# GPIO_adaptator.net
KiCad netlist of a schematic drawn in EAGLE
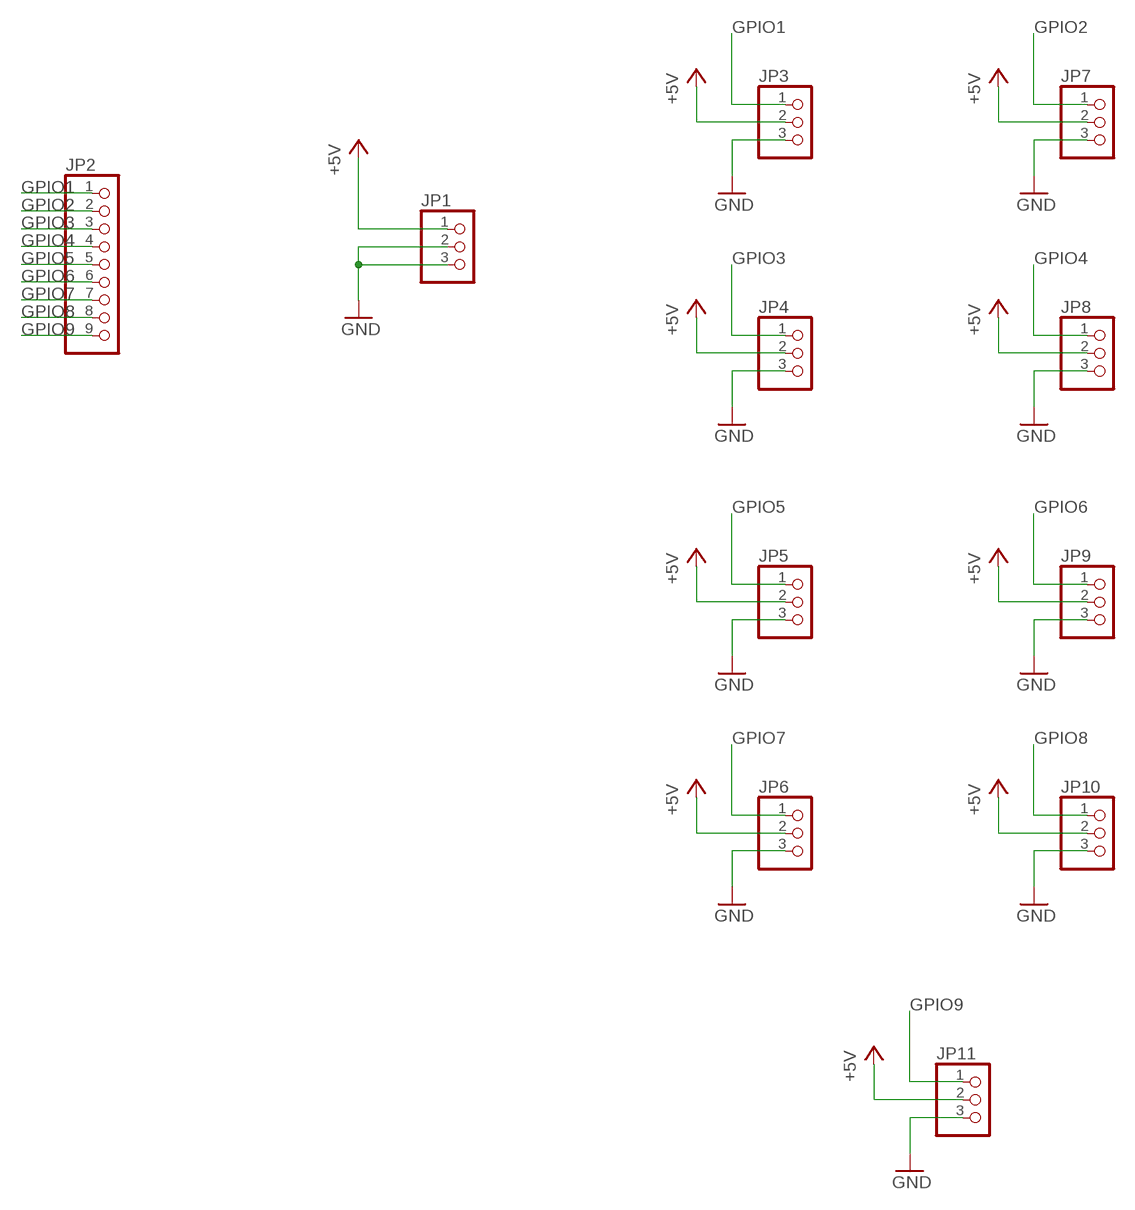
[diagram p0: schematic, sheet 1]

(export (version "E")
  (design (tool "Eeschema 10.0.6"))
  (components
    (comp (ref "JP1")
      (value "PINHD-1X3")
      (footprint "eagle-import:1X03")
      (libsource (lib "eagle-import") (part "PINHD-1X3"))
    )
    (comp (ref "JP2")
      (value "PINHD-1X9")
      (footprint "eagle-import:1X09")
      (libsource (lib "eagle-import") (part "PINHD-1X9"))
    )
    (comp (ref "JP3")
      (value "PINHD-1X3")
      (footprint "eagle-import:1X03")
      (libsource (lib "eagle-import") (part "PINHD-1X3"))
    )
    (comp (ref "JP4")
      (value "PINHD-1X3")
      (footprint "eagle-import:1X03")
      (libsource (lib "eagle-import") (part "PINHD-1X3"))
    )
    (comp (ref "JP5")
      (value "PINHD-1X3")
      (footprint "eagle-import:1X03")
      (libsource (lib "eagle-import") (part "PINHD-1X3"))
    )
    (comp (ref "JP6")
      (value "PINHD-1X3")
      (footprint "eagle-import:1X03")
      (libsource (lib "eagle-import") (part "PINHD-1X3"))
    )
    (comp (ref "JP7")
      (value "PINHD-1X3")
      (footprint "eagle-import:1X03")
      (libsource (lib "eagle-import") (part "PINHD-1X3"))
    )
    (comp (ref "JP8")
      (value "PINHD-1X3")
      (footprint "eagle-import:1X03")
      (libsource (lib "eagle-import") (part "PINHD-1X3"))
    )
    (comp (ref "JP9")
      (value "PINHD-1X3")
      (footprint "eagle-import:1X03")
      (libsource (lib "eagle-import") (part "PINHD-1X3"))
    )
    (comp (ref "JP10")
      (value "PINHD-1X3")
      (footprint "eagle-import:1X03")
      (libsource (lib "eagle-import") (part "PINHD-1X3"))
    )
    (comp (ref "JP11")
      (value "PINHD-1X3")
      (footprint "eagle-import:1X03")
      (libsource (lib "eagle-import") (part "PINHD-1X3"))
    )
  )
  (nets
    (net (code "1") (name "+5V") (class "Default")
      (node (ref "JP1") (pin "1") (pinfunction "1_1") (pintype "passive"))
      (node (ref "JP10") (pin "2") (pinfunction "2_2") (pintype "passive"))
      (node (ref "JP11") (pin "2") (pinfunction "2_2") (pintype "passive"))
      (node (ref "JP3") (pin "2") (pinfunction "2_2") (pintype "passive"))
      (node (ref "JP4") (pin "2") (pinfunction "2_2") (pintype "passive"))
      (node (ref "JP5") (pin "2") (pinfunction "2_2") (pintype "passive"))
      (node (ref "JP6") (pin "2") (pinfunction "2_2") (pintype "passive"))
      (node (ref "JP7") (pin "2") (pinfunction "2_2") (pintype "passive"))
      (node (ref "JP8") (pin "2") (pinfunction "2_2") (pintype "passive"))
      (node (ref "JP9") (pin "2") (pinfunction "2_2") (pintype "passive"))
    )
    (net (code "2") (name "/GPIO1") (class "Default")
      (node (ref "JP2") (pin "1") (pinfunction "1_1") (pintype "passive"))
      (node (ref "JP3") (pin "1") (pinfunction "1_1") (pintype "passive"))
    )
    (net (code "3") (name "/GPIO2") (class "Default")
      (node (ref "JP2") (pin "2") (pinfunction "2_2") (pintype "passive"))
      (node (ref "JP7") (pin "1") (pinfunction "1_1") (pintype "passive"))
    )
    (net (code "4") (name "/GPIO3") (class "Default")
      (node (ref "JP2") (pin "3") (pinfunction "3_3") (pintype "passive"))
      (node (ref "JP4") (pin "1") (pinfunction "1_1") (pintype "passive"))
    )
    (net (code "5") (name "/GPIO4") (class "Default")
      (node (ref "JP2") (pin "4") (pinfunction "4_4") (pintype "passive"))
      (node (ref "JP8") (pin "1") (pinfunction "1_1") (pintype "passive"))
    )
    (net (code "6") (name "/GPIO5") (class "Default")
      (node (ref "JP2") (pin "5") (pinfunction "5_5") (pintype "passive"))
      (node (ref "JP5") (pin "1") (pinfunction "1_1") (pintype "passive"))
    )
    (net (code "7") (name "/GPIO6") (class "Default")
      (node (ref "JP2") (pin "6") (pinfunction "6_6") (pintype "passive"))
      (node (ref "JP9") (pin "1") (pinfunction "1_1") (pintype "passive"))
    )
    (net (code "8") (name "/GPIO7") (class "Default")
      (node (ref "JP2") (pin "7") (pinfunction "7_7") (pintype "passive"))
      (node (ref "JP6") (pin "1") (pinfunction "1_1") (pintype "passive"))
    )
    (net (code "9") (name "/GPIO8") (class "Default")
      (node (ref "JP10") (pin "1") (pinfunction "1_1") (pintype "passive"))
      (node (ref "JP2") (pin "8") (pinfunction "8_8") (pintype "passive"))
    )
    (net (code "10") (name "/GPIO9") (class "Default")
      (node (ref "JP11") (pin "1") (pinfunction "1_1") (pintype "passive"))
      (node (ref "JP2") (pin "9") (pinfunction "9_9") (pintype "passive"))
    )
    (net (code "11") (name "GND") (class "Default")
      (node (ref "JP1") (pin "2") (pinfunction "2_2") (pintype "passive"))
      (node (ref "JP1") (pin "3") (pinfunction "3_3") (pintype "passive"))
      (node (ref "JP10") (pin "3") (pinfunction "3_3") (pintype "passive"))
      (node (ref "JP11") (pin "3") (pinfunction "3_3") (pintype "passive"))
      (node (ref "JP3") (pin "3") (pinfunction "3_3") (pintype "passive"))
      (node (ref "JP4") (pin "3") (pinfunction "3_3") (pintype "passive"))
      (node (ref "JP5") (pin "3") (pinfunction "3_3") (pintype "passive"))
      (node (ref "JP6") (pin "3") (pinfunction "3_3") (pintype "passive"))
      (node (ref "JP7") (pin "3") (pinfunction "3_3") (pintype "passive"))
      (node (ref "JP8") (pin "3") (pinfunction "3_3") (pintype "passive"))
      (node (ref "JP9") (pin "3") (pinfunction "3_3") (pintype "passive"))
    )
  )
)
